# power.net
KiCad netlist of a schematic drawn in Altium Designer
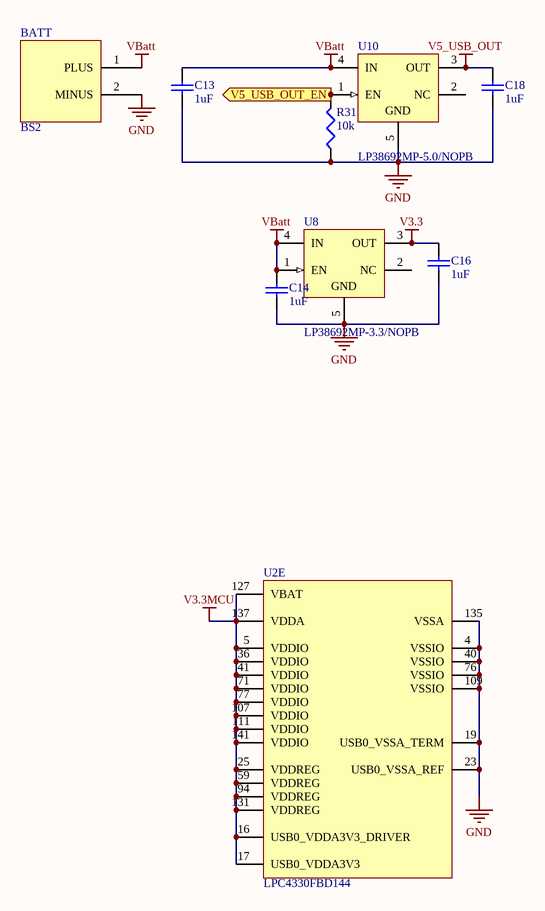
[diagram p0: power.SchDoc]

(export (version "E")
  (design (tool "Eeschema 10.0.6"))
  (components
    (comp (ref "BATT")
      (value "BS2")
      (footprint "PCBComponent_1")
      (libsource (lib "custom_for_quadrotor") (part "BS2"))
    )
    (comp (ref "C13")
      (value "1uF")
      (footprint "1608[0603]")
      (description "Capacitor (Semiconductor SIM Model)")
      (fields (field (name "PUBLISHER") "Altium Limited"))
      (libsource (lib "Miscellaneous Devices") (part "Cap Semi"))
    )
    (comp (ref "C14")
      (value "1uF")
      (footprint "1608[0603]")
      (description "Capacitor (Semiconductor SIM Model)")
      (fields (field (name "PUBLISHER") "Altium Limited"))
      (libsource (lib "Miscellaneous Devices") (part "Cap Semi"))
    )
    (comp (ref "C16")
      (value "1uF")
      (footprint "1608[0603]")
      (description "Capacitor (Semiconductor SIM Model)")
      (fields (field (name "PUBLISHER") "Altium Limited"))
      (libsource (lib "Miscellaneous Devices") (part "Cap Semi"))
    )
    (comp (ref "C18")
      (value "1uF")
      (footprint "1608[0603]")
      (description "Capacitor (Semiconductor SIM Model)")
      (fields (field (name "PUBLISHER") "Altium Limited"))
      (libsource (lib "Miscellaneous Devices") (part "Cap Semi"))
    )
    (comp (ref "R31")
      (value "10k")
      (footprint "J1-0603")
      (description "Resistor")
      (fields (field (name "PUBLISHER") "Altium Limited"))
      (libsource (lib "Miscellaneous Devices") (part "Res3"))
    )
    (comp (ref "U2")
      (value "LPC4330FBD144")
      (footprint "SOT486-1_V")
      (libsource (lib "NXP Semiconductors Cortex-M4") (part "LPC4330FBD144"))
    )
    (comp (ref "U8")
      (value "LP38692MP-3.3/NOPB")
      (footprint "MP05A_N")
      (fields (field (name "MANUFACTURER") "National Semiconductor"))
      (libsource (lib "National Semiconductor LDO") (part "LP38692MP-3.3/NOPB"))
    )
    (comp (ref "U10")
      (value "LP38692MP-5.0/NOPB")
      (footprint "MP05A_N")
      (fields (field (name "MANUFACTURER") "National Semiconductor"))
      (libsource (lib "National Semiconductor LDO") (part "LP38692MP-5.0/NOPB"))
    )
  )
  (nets
    (net (code "1") (name "/V5_USB_OUT_EN") (class "Default")
      (node (ref "R31") (pin "2") (pinfunction "2_2") (pintype "passive"))
      (node (ref "U10") (pin "1") (pinfunction "EN_1") (pintype "input"))
    )
    (net (code "2") (name "GND") (class "Default")
      (node (ref "BATT") (pin "2") (pinfunction "MINUS_2") (pintype "passive"))
      (node (ref "C13") (pin "1") (pinfunction "1_1") (pintype "passive"))
      (node (ref "C14") (pin "1") (pinfunction "1_1") (pintype "passive"))
      (node (ref "C16") (pin "1") (pinfunction "1_1") (pintype "passive"))
      (node (ref "C18") (pin "1") (pinfunction "1_1") (pintype "passive"))
      (node (ref "R31") (pin "1") (pinfunction "1_1") (pintype "passive"))
      (node (ref "U10") (pin "5") (pinfunction "GND_5") (pintype "power_in"))
      (node (ref "U2") (pin "109") (pinfunction "VSSIO_109") (pintype "power_in"))
      (node (ref "U2") (pin "135") (pinfunction "VSSA_135") (pintype "power_in"))
      (node (ref "U2") (pin "19") (pinfunction "USB0_VSSA_TERM_19") (pintype "power_in"))
      (node (ref "U2") (pin "23") (pinfunction "USB0_VSSA_REF_23") (pintype "power_in"))
      (node (ref "U2") (pin "4") (pinfunction "VSSIO_4") (pintype "power_in"))
      (node (ref "U2") (pin "40") (pinfunction "VSSIO_40") (pintype "power_in"))
      (node (ref "U2") (pin "76") (pinfunction "VSSIO_76") (pintype "power_in"))
      (node (ref "U8") (pin "5") (pinfunction "GND_5") (pintype "power_in"))
    )
    (net (code "3") (name "V3.3") (class "Default")
      (node (ref "C16") (pin "2") (pinfunction "2_2") (pintype "passive"))
      (node (ref "U8") (pin "3") (pinfunction "OUT_3") (pintype "power_in"))
    )
    (net (code "4") (name "V3.3MCU") (class "Default")
      (node (ref "U2") (pin "107") (pinfunction "VDDIO_107") (pintype "power_in"))
      (node (ref "U2") (pin "111") (pinfunction "VDDIO_111") (pintype "power_in"))
      (node (ref "U2") (pin "127") (pinfunction "VBAT_127") (pintype "power_in"))
      (node (ref "U2") (pin "131") (pinfunction "VDDREG_131") (pintype "power_in"))
      (node (ref "U2") (pin "137") (pinfunction "VDDA_137") (pintype "power_in"))
      (node (ref "U2") (pin "141") (pinfunction "VDDIO_141") (pintype "power_in"))
      (node (ref "U2") (pin "16") (pinfunction "USB0_VDDA3V3_DRIVER_16") (pintype "power_in"))
      (node (ref "U2") (pin "17") (pinfunction "USB0_VDDA3V3_17") (pintype "power_in"))
      (node (ref "U2") (pin "25") (pinfunction "VDDREG_25") (pintype "power_in"))
      (node (ref "U2") (pin "36") (pinfunction "VDDIO_36") (pintype "power_in"))
      (node (ref "U2") (pin "41") (pinfunction "VDDIO_41") (pintype "power_in"))
      (node (ref "U2") (pin "5") (pinfunction "VDDIO_5") (pintype "power_in"))
      (node (ref "U2") (pin "59") (pinfunction "VDDREG_59") (pintype "power_in"))
      (node (ref "U2") (pin "71") (pinfunction "VDDIO_71") (pintype "power_in"))
      (node (ref "U2") (pin "77") (pinfunction "VDDIO_77") (pintype "power_in"))
      (node (ref "U2") (pin "94") (pinfunction "VDDREG_94") (pintype "power_in"))
    )
    (net (code "5") (name "V5_USB_OUT") (class "Default")
      (node (ref "C18") (pin "2") (pinfunction "2_2") (pintype "passive"))
      (node (ref "U10") (pin "3") (pinfunction "OUT_3") (pintype "power_in"))
    )
    (net (code "6") (name "VBatt") (class "Default")
      (node (ref "BATT") (pin "1") (pinfunction "PLUS_1") (pintype "passive"))
      (node (ref "C13") (pin "2") (pinfunction "2_2") (pintype "passive"))
      (node (ref "C14") (pin "2") (pinfunction "2_2") (pintype "passive"))
      (node (ref "U10") (pin "4") (pinfunction "IN_4") (pintype "power_in"))
      (node (ref "U8") (pin "1") (pinfunction "EN_1") (pintype "input"))
      (node (ref "U8") (pin "4") (pinfunction "IN_4") (pintype "power_in"))
    )
    (net (code "7") (name "unconnected-(U8-NC-Pad2)") (class "Default")
      (node (ref "U8") (pin "2") (pinfunction "NC_2") (pintype "passive"))
    )
    (net (code "8") (name "unconnected-(U10-NC-Pad2)") (class "Default")
      (node (ref "U10") (pin "2") (pinfunction "NC_2") (pintype "passive"))
    )
  )
)
